# MCU.net
KiCad netlist of a schematic drawn in Altium Designer
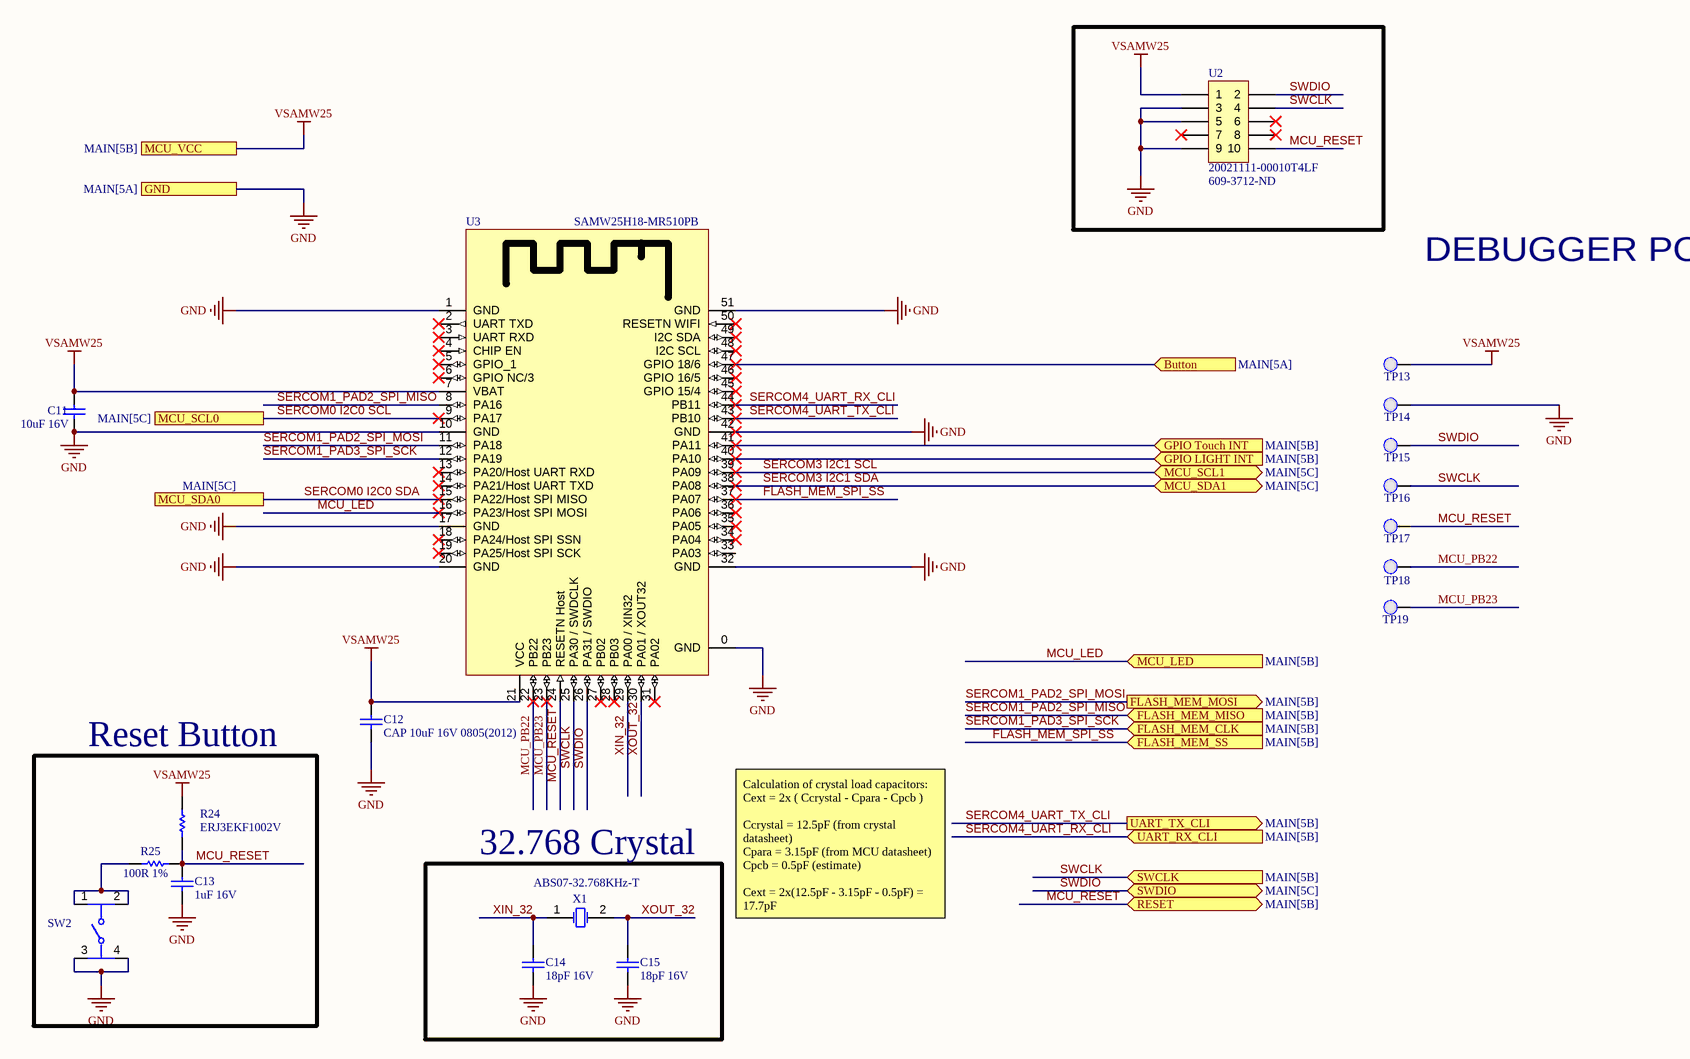
[diagram p0: MCU.SchDoc]

(export (version "E")
  (design (tool "Eeschema 10.0.6"))
  (components
    (comp (ref "C11")
      (value "10uF 16V")
      (footprint "CAPC0805(2012)145_N")
      (description "CAP 10uF 16V ±10% 0805 (2012 Metric) Thickness 1.45mm SMD")
      (fields (field (name "TOLERANCE") "Â±10%"))
      (libsource (lib "Altium Content Vault") (part "CAP"))
    )
    (comp (ref "C12")
      (value "CAP 10uF 16V 0805(2012)")
      (footprint "CAPC0805(2012)145_N")
      (description "CAP 10uF 16V ±10% 0805 (2012 Metric) Thickness 1.45mm SMD")
      (fields (field (name "TOLERANCE") "Â±10%"))
      (libsource (lib "Altium Content Vault") (part "CAP"))
    )
    (comp (ref "C13")
      (value "1uF 16V")
      (footprint "CAPC0603(1608)100_N")
      (description "CAP 1uF 16V ±5% 0603 (1608 Metric) Thickness 1mm SMD")
      (fields (field (name "TOLERANCE") "Â±5%"))
      (libsource (lib "Altium Content Vault") (part "CAP"))
    )
    (comp (ref "C14")
      (value "18pF 16V")
      (footprint "CAPC0603(1608)100_N")
      (description "CAP 18pF 16V ±5% 0603 (1608 Metric) Thickness 1mm SMD")
      (fields (field (name "TOLERANCE") "Â±5%"))
      (libsource (lib "Altium Content Vault") (part "CAP"))
    )
    (comp (ref "C15")
      (value "18pF 16V")
      (footprint "CAPC0603(1608)100_N")
      (description "CAP 18pF 16V ±5% 0603 (1608 Metric) Thickness 1mm SMD")
      (fields (field (name "TOLERANCE") "Â±5%"))
      (libsource (lib "Altium Content Vault") (part "CAP"))
    )
    (comp (ref "R24")
      (value "ERJ3EKF1002V")
      (footprint "RESC1609X55X30LL15T15")
      (description "Chip Resistor, 10 KOhm, +/- 1%, 0.1 W, -55 to 155 degC, 0603 (1608 Metric), RoHS, Tape and Reel")
      (fields (field (name "TOLERANCE") "1%") (field (name "MANUFACTURER") "Panasonic"))
      (libsource (lib "Altium Content Vault") (part "RES-2"))
    )
    (comp (ref "R25")
      (value "100R 1%")
      (footprint "RESC0603(1608)_N")
      (description "100R 0.1W 1% 0603 (1608 Metric)  SMD")
      (fields (field (name "TOLERANCE") "1 %") (field (name "POWER") "0.1 W"))
      (libsource (lib "Altium Content Vault") (part "RES"))
    )
    (comp (ref "SW2")
      (value "PTS810 SJG 250 SMTR LFS")
      (footprint "FP-PTS810_SJG_250_SMTR_LF-MFG")
      (description "SWITCH TACTILE SPST-NO 0.05A 16V")
      (fields
        (field (name "MANUFACTURER") "C&K Components")
        (field (name "OCTOPART") "https://octopart.com/pts810sjg250smtrlfs-c%26k+components-29380277")
      )
      (libsource (lib "Altium Content Vault") (part "1adf0dd01260c80cf25a44bfd6b99ba"))
    )
    (comp (ref "TP13")
      (value "0.1\" Pad")
      (footprint "PCBComponent")
      (libsource (lib "Components - 12.02.20 - 18.05") (part "0.1{dblquote} Pad-A.4"))
    )
    (comp (ref "TP14")
      (value "0.1\" Pad")
      (footprint "PCBComponent")
      (libsource (lib "Components - 12.02.20 - 18.05") (part "0.1{dblquote} Pad-A.4"))
    )
    (comp (ref "TP15")
      (value "0.1\" Pad")
      (footprint "PCBComponent")
      (libsource (lib "Components - 12.02.20 - 18.05") (part "0.1{dblquote} Pad-A.4"))
    )
    (comp (ref "TP16")
      (value "0.1\" Pad")
      (footprint "PCBComponent")
      (libsource (lib "Components - 12.02.20 - 18.05") (part "0.1{dblquote} Pad-A.4"))
    )
    (comp (ref "TP17")
      (value "0.1\" Pad")
      (footprint "PCBComponent")
      (libsource (lib "Components - 12.02.20 - 18.05") (part "0.1{dblquote} Pad-A.4"))
    )
    (comp (ref "TP18")
      (value "0.1\" Pad")
      (footprint "PCBComponent")
      (libsource (lib "Components - 12.02.20 - 18.05") (part "0.1{dblquote} Pad-A.4"))
    )
    (comp (ref "TP19")
      (value "0.1\" Pad")
      (footprint "PCBComponent")
      (libsource (lib "Components - 12.02.20 - 18.05") (part "0.1{dblquote} Pad-A.4"))
    )
    (comp (ref "U2")
      (value "20021111-00010T4LF")
      (footprint "20021111-00010T4LF")
      (description "CONN HEADER 10POS UNSHD VERT T/H")
      (fields
        (field (name "MANUFACTURER") "Amphenol / FCI")
        (field (name "SUPPLIER PART NUMBER 1") "609-3712-ND")
      )
      (libsource (lib "Schematics") (part "20021111-00010T4LF"))
    )
    (comp (ref "U3")
      (value "SAMW25H18-MR510PB")
      (footprint "SAMW25H18-MR510PB")
      (description "RF TXRX MODULE WIFI TRACE ANT")
      (fields
        (field (name "MANUFACTURER") "Atmel")
        (field (name "MANUFACTURER PART NUMBER") "ATSAMW25H18-MR510PB")
      )
      (libsource (lib "Schematics") (part "SAMW25H18-MR510PB"))
    )
    (comp (ref "X1")
      (value "ABS07-32.768KHz-T")
      (footprint "ABRA-ABS07-2_V")
      (description "Crystal, 32.768 kHz, 12.5 pF, -40 to 85 degC, SMD Low Profile 3.2 x 1.5 x 0.9 mm, Tape and Reel")
      (fields (field (name "MANUFACTURER") "Abracon"))
      (libsource (lib "Altium Content Vault") (part "ABRA-ABS07-2"))
    )
  )
  (nets
    (net (code "1") (name "/Button") (class "Default")
      (node (ref "U3") (pin "47") (pinfunction "GPIO_18/6_47") (pintype "bidirectional+no_connect"))
    )
    (net (code "2") (name "/FLASH_MEM_SPI_SS") (class "Default")
      (node (ref "U3") (pin "37") (pinfunction "PA07_37") (pintype "bidirectional+no_connect"))
    )
    (net (code "3") (name "/GPIO LIGHT INT") (class "Default")
      (node (ref "U3") (pin "40") (pinfunction "PA10_40") (pintype "bidirectional+no_connect"))
    )
    (net (code "4") (name "/GPIO Touch INT") (class "Default")
      (node (ref "U3") (pin "41") (pinfunction "PA11_41") (pintype "bidirectional+no_connect"))
    )
    (net (code "5") (name "/MCU_LED") (class "Default")
      (node (ref "U3") (pin "16") (pinfunction "PA23/Host_SPI_MOSI_16") (pintype "bidirectional+no_connect"))
    )
    (net (code "6") (name "/MCU_PB22") (class "Default")
      (node (ref "TP18") (pin "1") (pinfunction "PAD_1") (pintype "passive"))
      (node (ref "U3") (pin "22") (pinfunction "PB22_22") (pintype "bidirectional"))
    )
    (net (code "7") (name "/MCU_PB23") (class "Default")
      (node (ref "TP19") (pin "1") (pinfunction "PAD_1") (pintype "passive"))
      (node (ref "U3") (pin "23") (pinfunction "PB23_23") (pintype "bidirectional"))
    )
    (net (code "8") (name "/MCU_RESET") (class "Default")
      (node (ref "C13") (pin "2") (pinfunction "2_2") (pintype "passive"))
      (node (ref "R24") (pin "1") (pinfunction "1_1") (pintype "passive"))
      (node (ref "R25") (pin "2") (pinfunction "2_2") (pintype "passive"))
      (node (ref "TP17") (pin "1") (pinfunction "PAD_1") (pintype "passive"))
      (node (ref "U2") (pin "10") (pinfunction "10_10") (pintype "passive"))
      (node (ref "U3") (pin "24") (pinfunction "RESETN_Host_24") (pintype "input"))
    )
    (net (code "9") (name "/SERCOM0 I2C0 SCL") (class "Default")
      (node (ref "U3") (pin "9") (pinfunction "PA17_9") (pintype "bidirectional+no_connect"))
    )
    (net (code "10") (name "/SERCOM0 I2C0 SDA") (class "Default")
      (node (ref "U3") (pin "15") (pinfunction "PA22/Host_SPI_MISO_15") (pintype "bidirectional+no_connect"))
    )
    (net (code "11") (name "/SERCOM1_PAD2_SPI_MISO") (class "Default")
      (node (ref "U3") (pin "8") (pinfunction "PA16_8") (pintype "bidirectional"))
    )
    (net (code "12") (name "/SERCOM1_PAD2_SPI_MOSI") (class "Default")
      (node (ref "U3") (pin "11") (pinfunction "PA18_11") (pintype "bidirectional"))
    )
    (net (code "13") (name "/SERCOM1_PAD3_SPI_SCK") (class "Default")
      (node (ref "U3") (pin "12") (pinfunction "PA19_12") (pintype "bidirectional"))
    )
    (net (code "14") (name "/SERCOM3 I2C1 SCL") (class "Default")
      (node (ref "U3") (pin "39") (pinfunction "PA09_39") (pintype "bidirectional+no_connect"))
    )
    (net (code "15") (name "/SERCOM3 I2C1 SDA") (class "Default")
      (node (ref "U3") (pin "38") (pinfunction "PA08_38") (pintype "bidirectional+no_connect"))
    )
    (net (code "16") (name "/SERCOM4_UART_RX_CLI") (class "Default")
      (node (ref "U3") (pin "44") (pinfunction "PB11_44") (pintype "bidirectional+no_connect"))
    )
    (net (code "17") (name "/SERCOM4_UART_TX_CLI") (class "Default")
      (node (ref "U3") (pin "43") (pinfunction "PB10_43") (pintype "bidirectional+no_connect"))
    )
    (net (code "18") (name "/SWCLK") (class "Default")
      (node (ref "TP16") (pin "1") (pinfunction "PAD_1") (pintype "passive"))
      (node (ref "U2") (pin "4") (pinfunction "4_4") (pintype "passive"))
      (node (ref "U3") (pin "25") (pinfunction "PA30_/_SWDCLK_25") (pintype "bidirectional"))
    )
    (net (code "19") (name "/SWDIO") (class "Default")
      (node (ref "TP15") (pin "1") (pinfunction "PAD_1") (pintype "passive"))
      (node (ref "U2") (pin "2") (pinfunction "2_2") (pintype "passive"))
      (node (ref "U3") (pin "26") (pinfunction "PA31_/_SWDIO_26") (pintype "bidirectional"))
    )
    (net (code "20") (name "/XIN_32") (class "Default")
      (node (ref "C14") (pin "2") (pinfunction "2_2") (pintype "passive"))
      (node (ref "U3") (pin "29") (pinfunction "PA00_/_XIN32_29") (pintype "bidirectional"))
      (node (ref "X1") (pin "1") (pinfunction "X1_1") (pintype "passive"))
    )
    (net (code "21") (name "/XOUT_32") (class "Default")
      (node (ref "C15") (pin "2") (pinfunction "2_2") (pintype "passive"))
      (node (ref "U3") (pin "30") (pinfunction "PA01_/_XOUT32_30") (pintype "bidirectional"))
      (node (ref "X1") (pin "2") (pinfunction "X2_2") (pintype "passive"))
    )
    (net (code "22") (name "GND") (class "Default")
      (node (ref "C11") (pin "1") (pinfunction "1_1") (pintype "passive"))
      (node (ref "C12") (pin "1") (pinfunction "1_1") (pintype "passive"))
      (node (ref "C13") (pin "1") (pinfunction "1_1") (pintype "passive"))
      (node (ref "C14") (pin "1") (pinfunction "1_1") (pintype "passive"))
      (node (ref "C15") (pin "1") (pinfunction "1_1") (pintype "passive"))
      (node (ref "SW2") (pin "3") (pinfunction "3_3") (pintype "passive"))
      (node (ref "SW2") (pin "4") (pinfunction "4_4") (pintype "passive"))
      (node (ref "TP14") (pin "1") (pinfunction "PAD_1") (pintype "passive"))
      (node (ref "U2") (pin "3") (pinfunction "3_3") (pintype "passive"))
      (node (ref "U2") (pin "5") (pinfunction "5_5") (pintype "passive"))
      (node (ref "U2") (pin "9") (pinfunction "9_9") (pintype "passive"))
      (node (ref "U3") (pin "0") (pinfunction "GND_0") (pintype "power_in"))
      (node (ref "U3") (pin "1") (pinfunction "GND_1") (pintype "power_in"))
      (node (ref "U3") (pin "10") (pinfunction "GND_10") (pintype "power_in"))
      (node (ref "U3") (pin "17") (pinfunction "GND_17") (pintype "power_in"))
      (node (ref "U3") (pin "20") (pinfunction "GND_20") (pintype "power_in"))
      (node (ref "U3") (pin "32") (pinfunction "GND_32") (pintype "power_in"))
      (node (ref "U3") (pin "42") (pinfunction "GND_42") (pintype "power_in"))
      (node (ref "U3") (pin "51") (pinfunction "GND_51") (pintype "power_in"))
    )
    (net (code "23") (name "Net-(R25-Pad1)") (class "Default")
      (node (ref "R25") (pin "1") (pinfunction "1_1") (pintype "passive"))
      (node (ref "SW2") (pin "1") (pinfunction "1_1") (pintype "passive"))
      (node (ref "SW2") (pin "2") (pinfunction "2_2") (pintype "passive"))
    )
    (net (code "24") (name "VSAMW25") (class "Default")
      (node (ref "C11") (pin "2") (pinfunction "2_2") (pintype "passive"))
      (node (ref "C12") (pin "2") (pinfunction "2_2") (pintype "passive"))
      (node (ref "R24") (pin "2") (pinfunction "2_2") (pintype "passive"))
      (node (ref "TP13") (pin "1") (pinfunction "PAD_1") (pintype "passive"))
      (node (ref "U2") (pin "1") (pinfunction "1_1") (pintype "passive"))
      (node (ref "U3") (pin "21") (pinfunction "VCC_21") (pintype "power_in"))
      (node (ref "U3") (pin "7") (pinfunction "VBAT_7") (pintype "power_in"))
    )
    (net (code "25") (name "unconnected-(U2-Pad6)") (class "Default")
      (node (ref "U2") (pin "6") (pinfunction "6_6") (pintype "passive+no_connect"))
    )
    (net (code "26") (name "unconnected-(U2-Pad7)") (class "Default")
      (node (ref "U2") (pin "7") (pinfunction "7_7") (pintype "passive+no_connect"))
    )
    (net (code "27") (name "unconnected-(U2-Pad8)") (class "Default")
      (node (ref "U2") (pin "8") (pinfunction "8_8") (pintype "passive+no_connect"))
    )
    (net (code "28") (name "unconnected-(U3-CHIP_EN-Pad4)") (class "Default")
      (node (ref "U3") (pin "4") (pinfunction "CHIP_EN_4") (pintype "input+no_connect"))
    )
    (net (code "29") (name "unconnected-(U3-GPIO_1-Pad5)") (class "Default")
      (node (ref "U3") (pin "5") (pinfunction "GPIO_1_5") (pintype "bidirectional+no_connect"))
    )
    (net (code "30") (name "unconnected-(U3-GPIO_15{slash}4-Pad45)") (class "Default")
      (node (ref "U3") (pin "45") (pinfunction "GPIO_15/4_45") (pintype "bidirectional+no_connect"))
    )
    (net (code "31") (name "unconnected-(U3-GPIO_16{slash}5-Pad46)") (class "Default")
      (node (ref "U3") (pin "46") (pinfunction "GPIO_16/5_46") (pintype "bidirectional+no_connect"))
    )
    (net (code "32") (name "unconnected-(U3-GPIO_NC{slash}3-Pad6)") (class "Default")
      (node (ref "U3") (pin "6") (pinfunction "GPIO_NC/3_6") (pintype "bidirectional+no_connect"))
    )
    (net (code "33") (name "unconnected-(U3-I2C_SCL-Pad48)") (class "Default")
      (node (ref "U3") (pin "48") (pinfunction "I2C_SCL_48") (pintype "bidirectional+no_connect"))
    )
    (net (code "34") (name "unconnected-(U3-I2C_SDA-Pad49)") (class "Default")
      (node (ref "U3") (pin "49") (pinfunction "I2C_SDA_49") (pintype "bidirectional+no_connect"))
    )
    (net (code "35") (name "unconnected-(U3-PA02-Pad31)") (class "Default")
      (node (ref "U3") (pin "31") (pinfunction "PA02_31") (pintype "bidirectional+no_connect"))
    )
    (net (code "36") (name "unconnected-(U3-PA03-Pad33)") (class "Default")
      (node (ref "U3") (pin "33") (pinfunction "PA03_33") (pintype "bidirectional"))
    )
    (net (code "37") (name "unconnected-(U3-PA04-Pad34)") (class "Default")
      (node (ref "U3") (pin "34") (pinfunction "PA04_34") (pintype "bidirectional+no_connect"))
    )
    (net (code "38") (name "unconnected-(U3-PA05-Pad35)") (class "Default")
      (node (ref "U3") (pin "35") (pinfunction "PA05_35") (pintype "bidirectional+no_connect"))
    )
    (net (code "39") (name "unconnected-(U3-PA06-Pad36)") (class "Default")
      (node (ref "U3") (pin "36") (pinfunction "PA06_36") (pintype "bidirectional+no_connect"))
    )
    (net (code "40") (name "unconnected-(U3-PA20{slash}Host_UART_RXD-Pad13)") (class "Default")
      (node (ref "U3") (pin "13") (pinfunction "PA20/Host_UART_RXD_13") (pintype "bidirectional+no_connect"))
    )
    (net (code "41") (name "unconnected-(U3-PA21{slash}Host_UART_TXD-Pad14)") (class "Default")
      (node (ref "U3") (pin "14") (pinfunction "PA21/Host_UART_TXD_14") (pintype "bidirectional+no_connect"))
    )
    (net (code "42") (name "unconnected-(U3-PA24{slash}Host_SPI_SSN-Pad18)") (class "Default")
      (node (ref "U3") (pin "18") (pinfunction "PA24/Host_SPI_SSN_18") (pintype "bidirectional+no_connect"))
    )
    (net (code "43") (name "unconnected-(U3-PA25{slash}Host_SPI_SCK-Pad19)") (class "Default")
      (node (ref "U3") (pin "19") (pinfunction "PA25/Host_SPI_SCK_19") (pintype "bidirectional+no_connect"))
    )
    (net (code "44") (name "unconnected-(U3-PB02-Pad27)") (class "Default")
      (node (ref "U3") (pin "27") (pinfunction "PB02_27") (pintype "bidirectional+no_connect"))
    )
    (net (code "45") (name "unconnected-(U3-PB03-Pad28)") (class "Default")
      (node (ref "U3") (pin "28") (pinfunction "PB03_28") (pintype "bidirectional+no_connect"))
    )
    (net (code "46") (name "unconnected-(U3-RESETN_WIFI-Pad50)") (class "Default")
      (node (ref "U3") (pin "50") (pinfunction "RESETN_WIFI_50") (pintype "input+no_connect"))
    )
    (net (code "47") (name "unconnected-(U3-UART_RXD-Pad3)") (class "Default")
      (node (ref "U3") (pin "3") (pinfunction "UART_RXD_3") (pintype "input+no_connect"))
    )
    (net (code "48") (name "unconnected-(U3-UART_TXD-Pad2)") (class "Default")
      (node (ref "U3") (pin "2") (pinfunction "UART_TXD_2") (pintype "output+no_connect"))
    )
  )
)
